# 53L0-SATEL-I1.net
KiCad netlist of a schematic drawn in Altium Designer
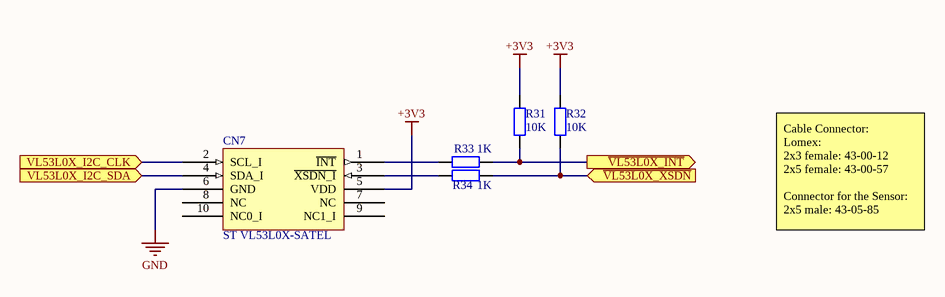
[diagram p0: 53L0-SATEL-I1.SchDoc]

(export (version "E")
  (design (tool "Eeschema 10.0.6"))
  (components
    (comp (ref "CN7")
      (value "ST VL53L0X-SATEL")
      (footprint "FP_DISTANCE_SENSOR")
      (description "53L0-SATEL-I1 satellite board for ranging sensor (max distance 2m)")
      (libsource (lib "LKBulls2023") (part "ST_53L0-SATEL-I1"))
    )
    (comp (ref "R31")
      (value "10K")
      (footprint "FP_0805_RES")
      (description "Resistor")
      (fields (field (name "TOLERANCE") "5%") (field (name "POWER") "0.125W"))
      (libsource (lib "") (part "RES_1"))
    )
    (comp (ref "R32")
      (value "10K")
      (footprint "FP_0805_RES")
      (description "Resistor")
      (fields (field (name "TOLERANCE") "5%") (field (name "POWER") "0.125W"))
      (libsource (lib "") (part "RES_1"))
    )
    (comp (ref "R33")
      (value "1K")
      (footprint "FP_0805_RES")
      (description "Resistor")
      (fields (field (name "TOLERANCE") "5%") (field (name "POWER") "0.125W"))
      (libsource (lib "LKBulls2023") (part "RES"))
    )
    (comp (ref "R34")
      (value "1K")
      (footprint "FP_0805_RES")
      (description "Resistor")
      (fields (field (name "TOLERANCE") "5%") (field (name "POWER") "0.125W"))
      (libsource (lib "LKBulls2023") (part "RES"))
    )
  )
  (nets
    (net (code "1") (name "+3V3") (class "Default")
      (node (ref "CN7") (pin "5") (pinfunction "VDD_5") (pintype "power_in"))
      (node (ref "R31") (pin "1") (pinfunction "1_1") (pintype "passive"))
      (node (ref "R32") (pin "1") (pinfunction "1_1") (pintype "passive"))
    )
    (net (code "2") (name "/VL53L0X_I2C_CLK") (class "Default")
      (node (ref "CN7") (pin "2") (pinfunction "SCL_I_2") (pintype "input"))
    )
    (net (code "3") (name "/VL53L0X_I2C_SDA") (class "Default")
      (node (ref "CN7") (pin "4") (pinfunction "SDA_I_4") (pintype "input"))
    )
    (net (code "4") (name "/~{VL53L0X_INT}") (class "Default")
      (node (ref "R31") (pin "2") (pinfunction "2_2") (pintype "passive"))
      (node (ref "R33") (pin "2") (pinfunction "2_2") (pintype "passive"))
    )
    (net (code "5") (name "/~{VL53L0X_XSDN}") (class "Default")
      (node (ref "R32") (pin "2") (pinfunction "2_2") (pintype "passive"))
      (node (ref "R34") (pin "2") (pinfunction "2_2") (pintype "passive"))
    )
    (net (code "6") (name "GND") (class "Default")
      (node (ref "CN7") (pin "6") (pinfunction "GND_6") (pintype "passive"))
    )
    (net (code "7") (name "Net-(CN7-~{INT})") (class "Default")
      (node (ref "CN7") (pin "1") (pinfunction "~{INT}_1") (pintype "output"))
      (node (ref "R33") (pin "1") (pinfunction "1_1") (pintype "passive"))
    )
    (net (code "8") (name "Net-(CN7-~{XSDN_I})") (class "Default")
      (node (ref "CN7") (pin "3") (pinfunction "~{XSDN_I}_3") (pintype "input"))
      (node (ref "R34") (pin "1") (pinfunction "1_1") (pintype "passive"))
    )
    (net (code "9") (name "unconnected-(CN7-NC-Pad7)") (class "Default")
      (node (ref "CN7") (pin "7") (pinfunction "NC_7") (pintype "passive"))
    )
    (net (code "10") (name "unconnected-(CN7-NC-Pad8)") (class "Default")
      (node (ref "CN7") (pin "8") (pinfunction "NC_8") (pintype "passive"))
    )
    (net (code "11") (name "unconnected-(CN7-NC0_I-Pad10)") (class "Default")
      (node (ref "CN7") (pin "10") (pinfunction "NC0_I_10") (pintype "passive"))
    )
    (net (code "12") (name "unconnected-(CN7-NC1_I-Pad9)") (class "Default")
      (node (ref "CN7") (pin "9") (pinfunction "NC1_I_9") (pintype "passive"))
    )
  )
)
